# Low_Voltage_Power_Supply.net
KiCad netlist of a schematic drawn in EAGLE
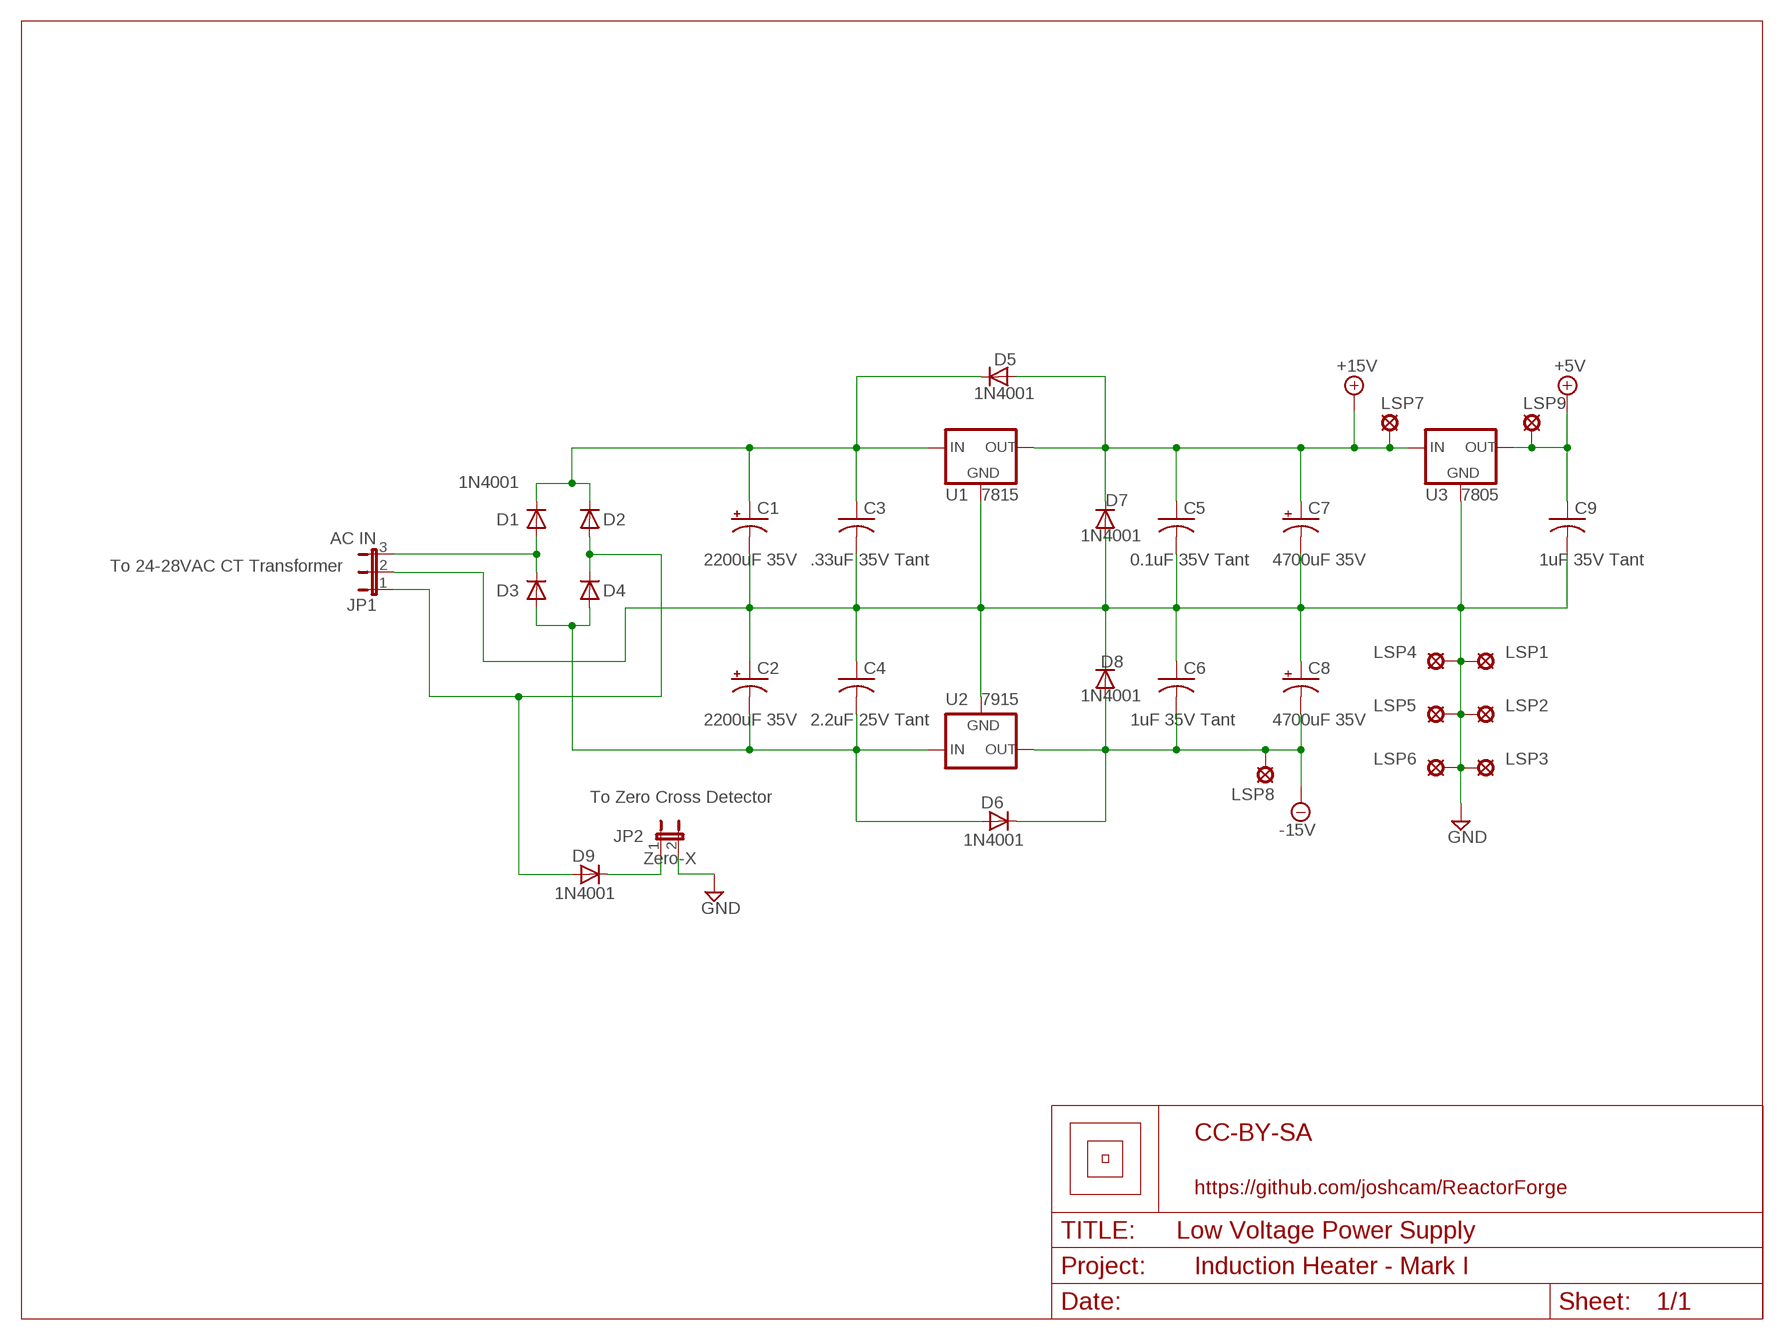
[diagram p0: schematic, sheet 1]

(export (version "E")
  (design (tool "Eeschema 10.0.6"))
  (components
    (comp (ref "C1")
      (value "2200uF 35V")
      (footprint "eagle-import:E7,5-18")
      (libsource (lib "eagle-import") (part "CPOL-USE7.5-18"))
    )
    (comp (ref "C2")
      (value "2200uF 35V")
      (footprint "eagle-import:E7,5-18")
      (libsource (lib "eagle-import") (part "CPOL-USE7.5-18"))
    )
    (comp (ref "C3")
      (value ".33uF 35V Tant")
      (footprint "eagle-import:C1206")
      (libsource (lib "eagle-import") (part "C-USC1206"))
    )
    (comp (ref "C4")
      (value "2.2uF 25V Tant")
      (footprint "eagle-import:C1206")
      (libsource (lib "eagle-import") (part "C-USC1206"))
    )
    (comp (ref "C5")
      (value "0.1uF 35V Tant")
      (footprint "eagle-import:C1206")
      (libsource (lib "eagle-import") (part "C-USC1206"))
    )
    (comp (ref "C6")
      (value "1uF 35V Tant")
      (footprint "eagle-import:C1206")
      (libsource (lib "eagle-import") (part "C-USC1206"))
    )
    (comp (ref "C7")
      (value "4700uF 35V")
      (footprint "eagle-import:E7,5-18")
      (libsource (lib "eagle-import") (part "CPOL-USE7.5-18"))
    )
    (comp (ref "C8")
      (value "4700uF 35V")
      (footprint "eagle-import:E7,5-18")
      (libsource (lib "eagle-import") (part "CPOL-USE7.5-18"))
    )
    (comp (ref "C9")
      (value "1uF 35V Tant")
      (footprint "eagle-import:C1206")
      (libsource (lib "eagle-import") (part "C-USC1206"))
    )
    (comp (ref "D1")
      (value "1N4001")
      (footprint "eagle-import:DIODE.4-AXIAL")
      (libsource (lib "eagle-import") (part "1N4001"))
    )
    (comp (ref "D2")
      (value "1N4001")
      (footprint "eagle-import:DIODE.4-AXIAL")
      (libsource (lib "eagle-import") (part "1N4001"))
    )
    (comp (ref "D3")
      (value "1N4001")
      (footprint "eagle-import:DIODE.4-AXIAL")
      (libsource (lib "eagle-import") (part "1N4001"))
    )
    (comp (ref "D4")
      (value "1N4001")
      (footprint "eagle-import:DIODE.4-AXIAL")
      (libsource (lib "eagle-import") (part "1N4001"))
    )
    (comp (ref "D5")
      (value "1N4001")
      (footprint "eagle-import:DIODE.4-AXIAL")
      (libsource (lib "eagle-import") (part "1N4001"))
    )
    (comp (ref "D6")
      (value "1N4001")
      (footprint "eagle-import:DIODE.4-AXIAL")
      (libsource (lib "eagle-import") (part "1N4001"))
    )
    (comp (ref "D7")
      (value "1N4001")
      (footprint "eagle-import:DIODE.4-AXIAL")
      (libsource (lib "eagle-import") (part "1N4001"))
    )
    (comp (ref "D8")
      (value "1N4001")
      (footprint "eagle-import:DIODE.4-AXIAL")
      (libsource (lib "eagle-import") (part "1N4001"))
    )
    (comp (ref "D9")
      (value "1N4001")
      (footprint "eagle-import:DIODE.4-AXIAL")
      (libsource (lib "eagle-import") (part "1N4001"))
    )
    (comp (ref "JP1")
      (value "AC IN")
      (footprint "eagle-import:JP2")
      (libsource (lib "eagle-import") (part "JP2E"))
    )
    (comp (ref "JP2")
      (value "Zero-X")
      (footprint "eagle-import:JP1")
      (libsource (lib "eagle-import") (part "JP1E"))
    )
    (comp (ref "LSP1")
      (value "SE14")
      (footprint "eagle-import:SE14")
      (libsource (lib "eagle-import") (part "SE14"))
    )
    (comp (ref "LSP2")
      (value "SE14")
      (footprint "eagle-import:SE14")
      (libsource (lib "eagle-import") (part "SE14"))
    )
    (comp (ref "LSP3")
      (value "SE14")
      (footprint "eagle-import:SE14")
      (libsource (lib "eagle-import") (part "SE14"))
    )
    (comp (ref "LSP4")
      (value "SE14")
      (footprint "eagle-import:SE14")
      (libsource (lib "eagle-import") (part "SE14"))
    )
    (comp (ref "LSP5")
      (value "SE14")
      (footprint "eagle-import:SE14")
      (libsource (lib "eagle-import") (part "SE14"))
    )
    (comp (ref "LSP6")
      (value "SE14")
      (footprint "eagle-import:SE14")
      (libsource (lib "eagle-import") (part "SE14"))
    )
    (comp (ref "LSP7")
      (value "SE14")
      (footprint "eagle-import:SE14")
      (libsource (lib "eagle-import") (part "SE14"))
    )
    (comp (ref "LSP8")
      (value "SE14")
      (footprint "eagle-import:SE14")
      (libsource (lib "eagle-import") (part "SE14"))
    )
    (comp (ref "LSP9")
      (value "SE14")
      (footprint "eagle-import:SE14")
      (libsource (lib "eagle-import") (part "SE14"))
    )
    (comp (ref "U1")
      (value "7815")
      (footprint "eagle-import:78XXS")
      (libsource (lib "eagle-import") (part "78XXS"))
    )
    (comp (ref "U2")
      (value "7915")
      (footprint "eagle-import:79XXS")
      (libsource (lib "eagle-import") (part "79XXS"))
    )
    (comp (ref "U3")
      (value "7805")
      (footprint "eagle-import:78XXS")
      (libsource (lib "eagle-import") (part "78XXS"))
    )
  )
  (nets
    (net (code "1") (name "+5V") (class "Default")
      (node (ref "C9") (pin "1") (pinfunction "1_1") (pintype "passive"))
      (node (ref "LSP9") (pin "MP") (pinfunction "MP_MP") (pintype "passive"))
      (node (ref "U3") (pin "OUT") (pinfunction "OUT_OUT") (pintype "passive"))
    )
    (net (code "2") (name "+15V") (class "Default")
      (node (ref "C5") (pin "1") (pinfunction "1_1") (pintype "passive"))
      (node (ref "C7") (pin "+") (pinfunction "+_+") (pintype "passive"))
      (node (ref "D5") (pin "A") (pinfunction "A_A") (pintype "passive"))
      (node (ref "D7") (pin "C") (pinfunction "C_C") (pintype "passive"))
      (node (ref "LSP7") (pin "MP") (pinfunction "MP_MP") (pintype "passive"))
      (node (ref "U1") (pin "OUT") (pinfunction "OUT_OUT") (pintype "passive"))
      (node (ref "U3") (pin "IN") (pinfunction "IN_IN") (pintype "input"))
    )
    (net (code "3") (name "-15V") (class "Default")
      (node (ref "C6") (pin "2") (pinfunction "2_2") (pintype "passive"))
      (node (ref "C8") (pin "-") (pinfunction "-_-") (pintype "passive"))
      (node (ref "D6") (pin "C") (pinfunction "C_C") (pintype "passive"))
      (node (ref "D8") (pin "A") (pinfunction "A_A") (pintype "passive"))
      (node (ref "LSP8") (pin "MP") (pinfunction "MP_MP") (pintype "passive"))
      (node (ref "U2") (pin "OUT") (pinfunction "OUT_OUT") (pintype "passive"))
    )
    (net (code "4") (name "GND") (class "Default")
      (node (ref "C1") (pin "-") (pinfunction "-_-") (pintype "passive"))
      (node (ref "C2") (pin "+") (pinfunction "+_+") (pintype "passive"))
      (node (ref "C3") (pin "2") (pinfunction "2_2") (pintype "passive"))
      (node (ref "C4") (pin "1") (pinfunction "1_1") (pintype "passive"))
      (node (ref "C5") (pin "2") (pinfunction "2_2") (pintype "passive"))
      (node (ref "C6") (pin "1") (pinfunction "1_1") (pintype "passive"))
      (node (ref "C7") (pin "-") (pinfunction "-_-") (pintype "passive"))
      (node (ref "C8") (pin "+") (pinfunction "+_+") (pintype "passive"))
      (node (ref "C9") (pin "2") (pinfunction "2_2") (pintype "passive"))
      (node (ref "D7") (pin "A") (pinfunction "A_A") (pintype "passive"))
      (node (ref "D8") (pin "C") (pinfunction "C_C") (pintype "passive"))
      (node (ref "JP1") (pin "2") (pinfunction "2_2") (pintype "passive"))
      (node (ref "JP2") (pin "2") (pinfunction "2_2") (pintype "passive"))
      (node (ref "LSP1") (pin "MP") (pinfunction "MP_MP") (pintype "passive"))
      (node (ref "LSP2") (pin "MP") (pinfunction "MP_MP") (pintype "passive"))
      (node (ref "LSP3") (pin "MP") (pinfunction "MP_MP") (pintype "passive"))
      (node (ref "LSP4") (pin "MP") (pinfunction "MP_MP") (pintype "passive"))
      (node (ref "LSP5") (pin "MP") (pinfunction "MP_MP") (pintype "passive"))
      (node (ref "LSP6") (pin "MP") (pinfunction "MP_MP") (pintype "passive"))
      (node (ref "U1") (pin "GND") (pinfunction "GND_GND") (pintype "input"))
      (node (ref "U2") (pin "GND") (pinfunction "GND_GND") (pintype "input"))
      (node (ref "U3") (pin "GND") (pinfunction "GND_GND") (pintype "input"))
    )
    (net (code "5") (name "Net-(C1-Pad+)") (class "Default")
      (node (ref "C1") (pin "+") (pinfunction "+_+") (pintype "passive"))
      (node (ref "C3") (pin "1") (pinfunction "1_1") (pintype "passive"))
      (node (ref "D1") (pin "C") (pinfunction "C_C") (pintype "passive"))
      (node (ref "D2") (pin "C") (pinfunction "C_C") (pintype "passive"))
      (node (ref "D5") (pin "C") (pinfunction "C_C") (pintype "passive"))
      (node (ref "U1") (pin "IN") (pinfunction "IN_IN") (pintype "input"))
    )
    (net (code "6") (name "Net-(C2-Pad-)") (class "Default")
      (node (ref "C2") (pin "-") (pinfunction "-_-") (pintype "passive"))
      (node (ref "C4") (pin "2") (pinfunction "2_2") (pintype "passive"))
      (node (ref "D3") (pin "A") (pinfunction "A_A") (pintype "passive"))
      (node (ref "D4") (pin "A") (pinfunction "A_A") (pintype "passive"))
      (node (ref "D6") (pin "A") (pinfunction "A_A") (pintype "passive"))
      (node (ref "U2") (pin "IN") (pinfunction "IN_IN") (pintype "input"))
    )
    (net (code "7") (name "Net-(D1-PadA)") (class "Default")
      (node (ref "D1") (pin "A") (pinfunction "A_A") (pintype "passive"))
      (node (ref "D3") (pin "C") (pinfunction "C_C") (pintype "passive"))
      (node (ref "JP1") (pin "3") (pinfunction "3_3") (pintype "passive"))
    )
    (net (code "8") (name "Net-(D2-PadA)") (class "Default")
      (node (ref "D2") (pin "A") (pinfunction "A_A") (pintype "passive"))
      (node (ref "D4") (pin "C") (pinfunction "C_C") (pintype "passive"))
      (node (ref "D9") (pin "A") (pinfunction "A_A") (pintype "passive"))
      (node (ref "JP1") (pin "1") (pinfunction "1_1") (pintype "passive"))
    )
    (net (code "9") (name "Net-(D9-PadC)") (class "Default")
      (node (ref "D9") (pin "C") (pinfunction "C_C") (pintype "passive"))
      (node (ref "JP2") (pin "1") (pinfunction "1_1") (pintype "passive"))
    )
  )
)
